# INA220.net
KiCad netlist of a schematic drawn in Altium Designer
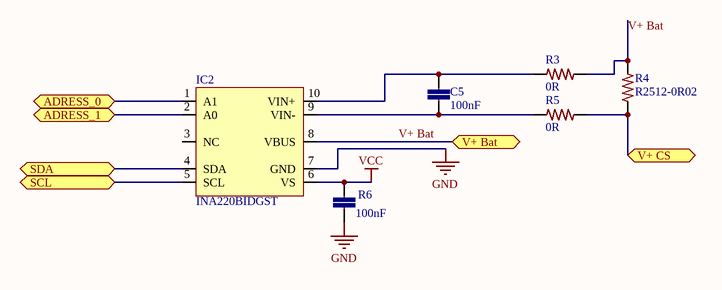
[diagram p0: INA220.SchDoc]

(export (version "E")
  (design (tool "Eeschema 10.0.6"))
  (components
    (comp (ref "C5")
      (value "100nF")
      (footprint "0402-CAP")
      (description "CAP CER 0.1UF 10V 20% X5R 0402")
      (fields (field (name "PART NO") "VJ0402V104ZXQPBC"))
      (libsource (lib "IMBEL") (part "CAPACITOR"))
    )
    (comp (ref "IC2")
      (value "INA220BIDGST")
      (footprint "TSSOP10")
      (description "IC MONITOR PWR/CURR BIDIR 10MSOP")
      (libsource (lib "IMBEL") (part "INA220BIDGST-3"))
    )
    (comp (ref "R3")
      (value "0R")
      (footprint "0402-RES-HD")
      (description "RES 0.0 OHM 1/16W JUMP 0402 SMD")
      (fields (field (name "PART NO") "CRCW04020000Z0ED"))
      (libsource (lib "IMBEL") (part "RESISTOR"))
    )
    (comp (ref "R4")
      (value "R2512-0R02")
      (footprint "2512-RES-HD")
      (description "RES .02 OHM 2W 1% 2512 SMD")
      (fields (field (name "PART NO") "WSL2512R0200FEA18"))
      (libsource (lib "IMBEL") (part "R2512-0R02-4"))
    )
    (comp (ref "R5")
      (value "0R")
      (footprint "0402-RES-HD")
      (description "RES 0.0 OHM 1/16W JUMP 0402 SMD")
      (fields (field (name "PART NO") "CRCW04020000Z0ED"))
      (libsource (lib "IMBEL") (part "RESISTOR"))
    )
    (comp (ref "R6")
      (value "100nF")
      (footprint "0402-CAP")
      (description "CAP CER 0.1UF 10V 20% X5R 0402")
      (fields (field (name "PART NO") "VJ0402V104ZXQPBC"))
      (libsource (lib "IMBEL") (part "CC0402-100nF-A.12"))
    )
  )
  (nets
    (net (code "1") (name "/ADRESS_0") (class "Default")
      (node (ref "IC2") (pin "1") (pinfunction "A1_1") (pintype "passive"))
    )
    (net (code "2") (name "/ADRESS_1") (class "Default")
      (node (ref "IC2") (pin "2") (pinfunction "A0_2") (pintype "passive"))
    )
    (net (code "3") (name "/SCL") (class "Default")
      (node (ref "IC2") (pin "5") (pinfunction "SCL_5") (pintype "passive"))
    )
    (net (code "4") (name "/SDA") (class "Default")
      (node (ref "IC2") (pin "4") (pinfunction "SDA_4") (pintype "passive"))
    )
    (net (code "5") (name "/V+ Bat") (class "Default")
      (node (ref "IC2") (pin "8") (pinfunction "VBUS_8") (pintype "passive"))
      (node (ref "R3") (pin "2") (pinfunction "2_2") (pintype "passive"))
      (node (ref "R4") (pin "2") (pinfunction "2_2") (pintype "passive"))
    )
    (net (code "6") (name "/V+ CS") (class "Default")
      (node (ref "R4") (pin "1") (pinfunction "1_1") (pintype "passive"))
      (node (ref "R5") (pin "2") (pinfunction "2_2") (pintype "passive"))
    )
    (net (code "7") (name "GND") (class "Default")
      (node (ref "IC2") (pin "7") (pinfunction "GND_7") (pintype "passive"))
      (node (ref "R6") (pin "2") (pinfunction "2_2") (pintype "passive"))
    )
    (net (code "8") (name "Net-(IC2-VIN+)") (class "Default")
      (node (ref "C5") (pin "1") (pinfunction "1_1") (pintype "passive"))
      (node (ref "IC2") (pin "10") (pinfunction "VIN+_10") (pintype "passive"))
      (node (ref "R3") (pin "1") (pinfunction "1_1") (pintype "passive"))
    )
    (net (code "9") (name "Net-(IC2-VIN-)") (class "Default")
      (node (ref "C5") (pin "2") (pinfunction "2_2") (pintype "passive"))
      (node (ref "IC2") (pin "9") (pinfunction "VIN-_9") (pintype "passive"))
      (node (ref "R5") (pin "1") (pinfunction "1_1") (pintype "passive"))
    )
    (net (code "10") (name "VCC") (class "Default")
      (node (ref "IC2") (pin "6") (pinfunction "VS_6") (pintype "passive"))
      (node (ref "R6") (pin "1") (pinfunction "1_1") (pintype "passive"))
    )
    (net (code "11") (name "unconnected-(IC2-NC-Pad3)") (class "Default")
      (node (ref "IC2") (pin "3") (pinfunction "NC_3") (pintype "passive"))
    )
  )
)
